# foraging_board.net
KiCad netlist of a schematic drawn in EAGLE
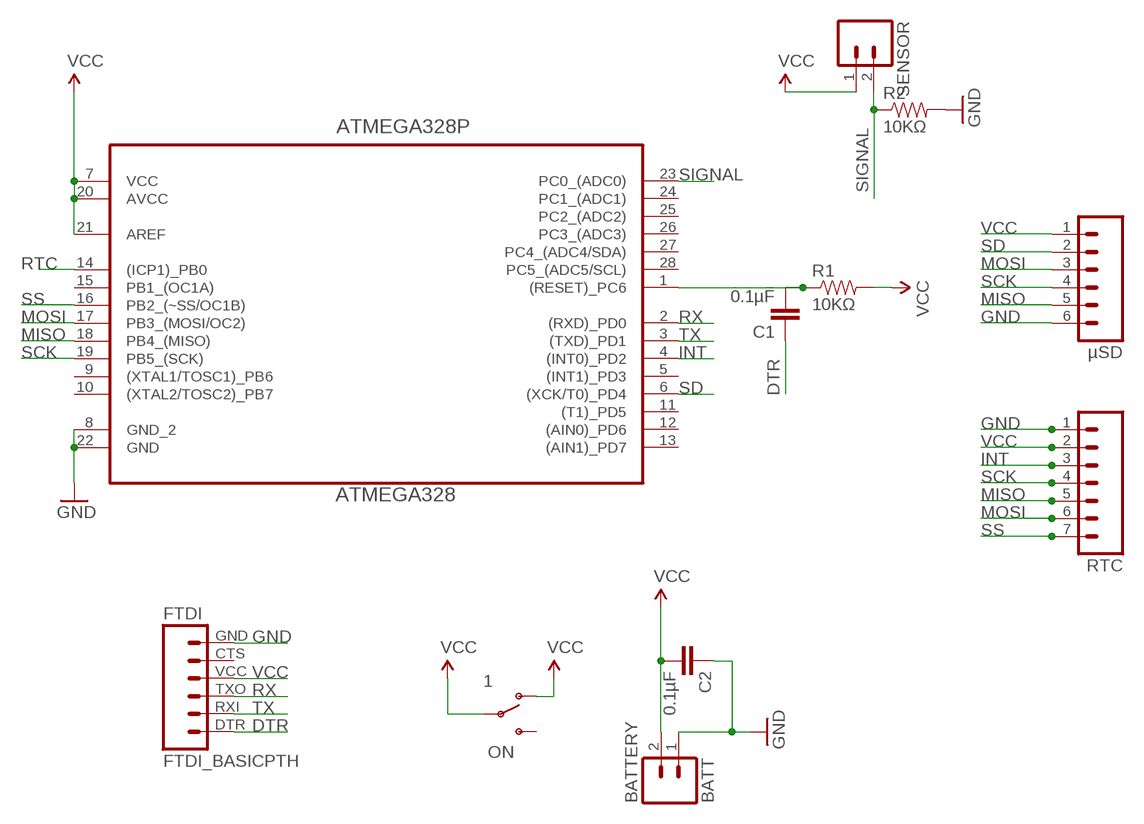
[diagram p0: schematic, sheet 1]

(export (version "E")
  (design (tool "Eeschema 10.0.6"))
  (components
    (comp (ref "ATMEGA328P")
      (value "ATMEGA328")
      (footprint "eagle-import:DIP254P762X457-28")
      (fields (field (name "MPN") "ATMEGA8L-8PU"))
      (libsource (lib "eagle-import") (part "ATMEGA8L-8PU"))
    )
    (comp (ref "BATTERY")
      (value "BATT")
      (footprint "eagle-import:JST-2-PTH-NS")
      (libsource (lib "eagle-import") (part "M02-JST-2-PTH-NO_SILK"))
    )
    (comp (ref "C1")
      (value "0.1µF")
      (footprint "eagle-import:CAP-PTH-SMALL-KIT")
      (libsource (lib "eagle-import") (part "0.1UF-50V-20%(PTH)KIT-EZ"))
    )
    (comp (ref "C2")
      (value "0.1µF")
      (footprint "eagle-import:CAP-PTH-SMALL-KIT")
      (libsource (lib "eagle-import") (part "0.1UF-50V-20%(PTH)KIT-EZ"))
    )
    (comp (ref "FTDI")
      (value "FTDI_BASICPTH")
      (footprint "eagle-import:FTDI_BASIC")
      (libsource (lib "eagle-import") (part "FTDI_BASICPTH"))
    )
    (comp (ref "ON")
      (value "1")
      (footprint "eagle-import:SWITCH-SPDT_KIT")
      (libsource (lib "eagle-import") (part "SWITCH-SPSTKIT"))
    )
    (comp (ref "R1")
      (value "10KΩ")
      (footprint "eagle-import:AXIAL-0.3EZ")
      (libsource (lib "eagle-import") (part "RESISTOREZ"))
    )
    (comp (ref "R2")
      (value "10KΩ")
      (footprint "eagle-import:AXIAL-0.3EZ")
      (libsource (lib "eagle-import") (part "RESISTOREZ"))
    )
    (comp (ref "RTC")
      (value "M07LONGPADS")
      (footprint "eagle-import:1X07_LONGPADS")
      (libsource (lib "eagle-import") (part "M07LONGPADS"))
    )
    (comp (ref "SENSOR")
      (value "M02PTH")
      (footprint "eagle-import:1X02")
      (libsource (lib "eagle-import") (part "M02PTH"))
    )
    (comp (ref "µSD")
      (value "M06LONGPADS")
      (footprint "eagle-import:1X06_LONGPADS")
      (libsource (lib "eagle-import") (part "M06LONGPADS"))
    )
  )
  (nets
    (net (code "1") (name "/DTR") (class "Default")
      (node (ref "C1") (pin "1") (pinfunction "1_1") (pintype "passive"))
      (node (ref "FTDI") (pin "DTR") (pinfunction "1_DTR") (pintype "passive"))
    )
    (net (code "2") (name "/INT") (class "Default")
      (node (ref "ATMEGA328P") (pin "4") (pinfunction "(INT0)_PD2_4") (pintype "bidirectional"))
      (node (ref "RTC") (pin "3") (pinfunction "3_3") (pintype "passive"))
    )
    (net (code "3") (name "/MISO") (class "Default")
      (node (ref "ATMEGA328P") (pin "18") (pinfunction "PB4_(MISO)_18") (pintype "bidirectional"))
      (node (ref "RTC") (pin "5") (pinfunction "5_5") (pintype "passive"))
      (node (ref "µSD") (pin "5") (pinfunction "5_5") (pintype "passive"))
    )
    (net (code "4") (name "/MOSI") (class "Default")
      (node (ref "ATMEGA328P") (pin "17") (pinfunction "PB3_(MOSI/OC2)_17") (pintype "bidirectional"))
      (node (ref "RTC") (pin "6") (pinfunction "6_6") (pintype "passive"))
      (node (ref "µSD") (pin "3") (pinfunction "3_3") (pintype "passive"))
    )
    (net (code "5") (name "/RTC") (class "Default")
      (node (ref "ATMEGA328P") (pin "14") (pinfunction "(ICP1)_PB0_14") (pintype "bidirectional"))
    )
    (net (code "6") (name "/RX") (class "Default")
      (node (ref "ATMEGA328P") (pin "2") (pinfunction "(RXD)_PD0_2") (pintype "bidirectional"))
      (node (ref "FTDI") (pin "TXO") (pinfunction "3_TXO") (pintype "passive"))
    )
    (net (code "7") (name "/SCK") (class "Default")
      (node (ref "ATMEGA328P") (pin "19") (pinfunction "PB5_(SCK)_19") (pintype "bidirectional"))
      (node (ref "RTC") (pin "4") (pinfunction "4_4") (pintype "passive"))
      (node (ref "µSD") (pin "4") (pinfunction "4_4") (pintype "passive"))
    )
    (net (code "8") (name "/SD") (class "Default")
      (node (ref "ATMEGA328P") (pin "6") (pinfunction "(XCK/T0)_PD4_6") (pintype "bidirectional"))
      (node (ref "µSD") (pin "2") (pinfunction "2_2") (pintype "passive"))
    )
    (net (code "9") (name "/SIGNAL") (class "Default")
      (node (ref "ATMEGA328P") (pin "23") (pinfunction "PC0_(ADC0)_23") (pintype "bidirectional"))
      (node (ref "R2") (pin "P$1") (pinfunction "1_P$1") (pintype "passive"))
      (node (ref "SENSOR") (pin "2") (pinfunction "2_2") (pintype "passive"))
    )
    (net (code "10") (name "/SS") (class "Default")
      (node (ref "ATMEGA328P") (pin "16") (pinfunction "PB2_(~{SS/OC1B})_16") (pintype "bidirectional"))
      (node (ref "RTC") (pin "7") (pinfunction "7_7") (pintype "passive"))
    )
    (net (code "11") (name "/TX") (class "Default")
      (node (ref "ATMEGA328P") (pin "3") (pinfunction "(TXD)_PD1_3") (pintype "bidirectional"))
      (node (ref "FTDI") (pin "RXI") (pinfunction "2_RXI") (pintype "passive"))
    )
    (net (code "12") (name "GND") (class "Default")
      (node (ref "ATMEGA328P") (pin "22") (pinfunction "GND_22") (pintype "passive"))
      (node (ref "ATMEGA328P") (pin "8") (pinfunction "GND_2_8") (pintype "passive"))
      (node (ref "BATTERY") (pin "1") (pinfunction "1_1") (pintype "passive"))
      (node (ref "C2") (pin "1") (pinfunction "1_1") (pintype "passive"))
      (node (ref "FTDI") (pin "GND") (pinfunction "6_GND") (pintype "passive"))
      (node (ref "R2") (pin "P$2") (pinfunction "2_P$2") (pintype "passive"))
      (node (ref "RTC") (pin "1") (pinfunction "1_1") (pintype "passive"))
      (node (ref "µSD") (pin "6") (pinfunction "6_6") (pintype "passive"))
    )
    (net (code "13") (name "Net-(ATMEGA328P-(RESET)_PC6)") (class "Default")
      (node (ref "ATMEGA328P") (pin "1") (pinfunction "(RESET)_PC6_1") (pintype "bidirectional"))
      (node (ref "C1") (pin "2") (pinfunction "2_2") (pintype "passive"))
      (node (ref "R1") (pin "P$1") (pinfunction "1_P$1") (pintype "passive"))
    )
    (net (code "14") (name "VCC") (class "Default")
      (node (ref "ATMEGA328P") (pin "20") (pinfunction "AVCC_20") (pintype "power_in"))
      (node (ref "ATMEGA328P") (pin "21") (pinfunction "AREF_21") (pintype "input"))
      (node (ref "ATMEGA328P") (pin "7") (pinfunction "VCC_7") (pintype "power_in"))
      (node (ref "BATTERY") (pin "2") (pinfunction "2_2") (pintype "passive"))
      (node (ref "C2") (pin "2") (pinfunction "2_2") (pintype "passive"))
      (node (ref "FTDI") (pin "VCC") (pinfunction "4_VCC") (pintype "passive"))
      (node (ref "ON") (pin "1") (pinfunction "O_1") (pintype "passive"))
      (node (ref "ON") (pin "2") (pinfunction "P_2") (pintype "passive"))
      (node (ref "R1") (pin "P$2") (pinfunction "2_P$2") (pintype "passive"))
      (node (ref "RTC") (pin "2") (pinfunction "2_2") (pintype "passive"))
      (node (ref "SENSOR") (pin "1") (pinfunction "1_1") (pintype "passive"))
      (node (ref "µSD") (pin "1") (pinfunction "1_1") (pintype "passive"))
    )
    (net (code "15") (name "unconnected-(ATMEGA328P-(AIN0)_PD6-Pad12)") (class "Default")
      (node (ref "ATMEGA328P") (pin "12") (pinfunction "(AIN0)_PD6_12") (pintype "bidirectional"))
    )
    (net (code "16") (name "unconnected-(ATMEGA328P-(AIN1)_PD7-Pad13)") (class "Default")
      (node (ref "ATMEGA328P") (pin "13") (pinfunction "(AIN1)_PD7_13") (pintype "bidirectional"))
    )
    (net (code "17") (name "unconnected-(ATMEGA328P-(INT1)_PD3-Pad5)") (class "Default")
      (node (ref "ATMEGA328P") (pin "5") (pinfunction "(INT1)_PD3_5") (pintype "bidirectional"))
    )
    (net (code "18") (name "unconnected-(ATMEGA328P-(T1)_PD5-Pad11)") (class "Default")
      (node (ref "ATMEGA328P") (pin "11") (pinfunction "(T1)_PD5_11") (pintype "bidirectional"))
    )
    (net (code "19") (name "unconnected-(ATMEGA328P-(XTAL1{slash}TOSC1)_PB6-Pad9)") (class "Default")
      (node (ref "ATMEGA328P") (pin "9") (pinfunction "(XTAL1/TOSC1)_PB6_9") (pintype "input"))
    )
    (net (code "20") (name "unconnected-(ATMEGA328P-(XTAL2{slash}TOSC2)_PB7-Pad10)") (class "Default")
      (node (ref "ATMEGA328P") (pin "10") (pinfunction "(XTAL2/TOSC2)_PB7_10") (pintype "input"))
    )
    (net (code "21") (name "unconnected-(ATMEGA328P-PB1_(OC1A)-Pad15)") (class "Default")
      (node (ref "ATMEGA328P") (pin "15") (pinfunction "PB1_(OC1A)_15") (pintype "bidirectional"))
    )
    (net (code "22") (name "unconnected-(ATMEGA328P-PC1_(ADC1)-Pad24)") (class "Default")
      (node (ref "ATMEGA328P") (pin "24") (pinfunction "PC1_(ADC1)_24") (pintype "bidirectional"))
    )
    (net (code "23") (name "unconnected-(ATMEGA328P-PC2_(ADC2)-Pad25)") (class "Default")
      (node (ref "ATMEGA328P") (pin "25") (pinfunction "PC2_(ADC2)_25") (pintype "bidirectional"))
    )
    (net (code "24") (name "unconnected-(ATMEGA328P-PC3_(ADC3)-Pad26)") (class "Default")
      (node (ref "ATMEGA328P") (pin "26") (pinfunction "PC3_(ADC3)_26") (pintype "bidirectional"))
    )
    (net (code "25") (name "unconnected-(ATMEGA328P-PC4_(ADC4{slash}SDA)-Pad27)") (class "Default")
      (node (ref "ATMEGA328P") (pin "27") (pinfunction "PC4_(ADC4/SDA)_27") (pintype "bidirectional"))
    )
    (net (code "26") (name "unconnected-(ATMEGA328P-PC5_(ADC5{slash}SCL)-Pad28)") (class "Default")
      (node (ref "ATMEGA328P") (pin "28") (pinfunction "PC5_(ADC5/SCL)_28") (pintype "bidirectional"))
    )
    (net (code "27") (name "unconnected-(FTDI-5-PadCTS)") (class "Default")
      (node (ref "FTDI") (pin "CTS") (pinfunction "5_CTS") (pintype "passive"))
    )
    (net (code "28") (name "unconnected-(ON-S-Pad3)") (class "Default")
      (node (ref "ON") (pin "3") (pinfunction "S_3") (pintype "passive"))
    )
  )
)
